# can_driver.net
KiCad netlist of a schematic drawn in Altium Designer
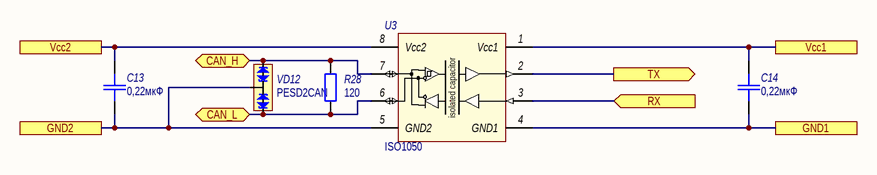
[diagram p0: can_driver.SchDoc]

(export (version "E")
  (design (tool "Eeschema 10.0.6"))
  (components
    (comp (ref "C13")
      (value "0,22мкФ")
      (footprint "SMD_0805")
      (description "Capacitor")
      (libsource (lib "Passive") (part "Capacitor"))
    )
    (comp (ref "C14")
      (value "0,22мкФ")
      (footprint "SMD_0805")
      (description "Capacitor")
      (libsource (lib "Passive") (part "Capacitor"))
    )
    (comp (ref "R28")
      (value "120")
      (footprint "SMD_0805")
      (description "Resistor")
      (libsource (lib "Passive") (part "Resistor"))
    )
    (comp (ref "U3")
      (value "ISO1050")
      (footprint "SOP-8")
      (description "Isolated CAN Transceiver")
      (fields (field (name "НАИМЕНОВАНИЕ") "ISO1050"))
      (libsource (lib "Transceiver") (part "ISO1050"))
    )
    (comp (ref "VD12")
      (value "PESD2CAN")
      (footprint "SOT-23")
      (description "CAN bus ESD protection diode")
      (fields (field (name "НАИМЕНОВАНИЕ") "PESD2CAN"))
      (libsource (lib "Diod") (part "PESD2CAN"))
    )
  )
  (nets
    (net (code "1") (name "/CAN_H") (class "Default")
      (node (ref "R28") (pin "2") (pinfunction "2_2") (pintype "passive"))
      (node (ref "U3") (pin "7") (pinfunction "ch_7") (pintype "bidirectional"))
      (node (ref "VD12") (pin "1") (pinfunction "C1_1") (pintype "passive"))
    )
    (net (code "2") (name "/CAN_L") (class "Default")
      (node (ref "R28") (pin "1") (pinfunction "1_1") (pintype "passive"))
      (node (ref "U3") (pin "6") (pinfunction "cl_6") (pintype "bidirectional"))
      (node (ref "VD12") (pin "2") (pinfunction "C2_2") (pintype "passive"))
    )
    (net (code "3") (name "/GND1") (class "Default")
      (node (ref "C14") (pin "1") (pinfunction "1_1") (pintype "passive"))
      (node (ref "U3") (pin "4") (pinfunction "GND1_4") (pintype "power_in"))
    )
    (net (code "4") (name "/GND2") (class "Default")
      (node (ref "C13") (pin "1") (pinfunction "1_1") (pintype "passive"))
      (node (ref "U3") (pin "5") (pinfunction "GND2_5") (pintype "power_in"))
      (node (ref "VD12") (pin "3") (pinfunction "CC_3") (pintype "passive"))
    )
    (net (code "5") (name "/RX") (class "Default")
      (node (ref "U3") (pin "3") (pinfunction "TXD_3") (pintype "input"))
    )
    (net (code "6") (name "/TX") (class "Default")
      (node (ref "U3") (pin "2") (pinfunction "RXD_2") (pintype "output"))
    )
    (net (code "7") (name "/Vcc1") (class "Default")
      (node (ref "C14") (pin "2") (pinfunction "2_2") (pintype "passive"))
      (node (ref "U3") (pin "1") (pinfunction "Vcc1_1") (pintype "power_in"))
    )
    (net (code "8") (name "/Vcc2") (class "Default")
      (node (ref "C13") (pin "2") (pinfunction "2_2") (pintype "passive"))
      (node (ref "U3") (pin "8") (pinfunction "Vcc2_8") (pintype "power_in"))
    )
  )
)
